# 07-ModuleControls.net
KiCad netlist of a schematic drawn in Altium Designer
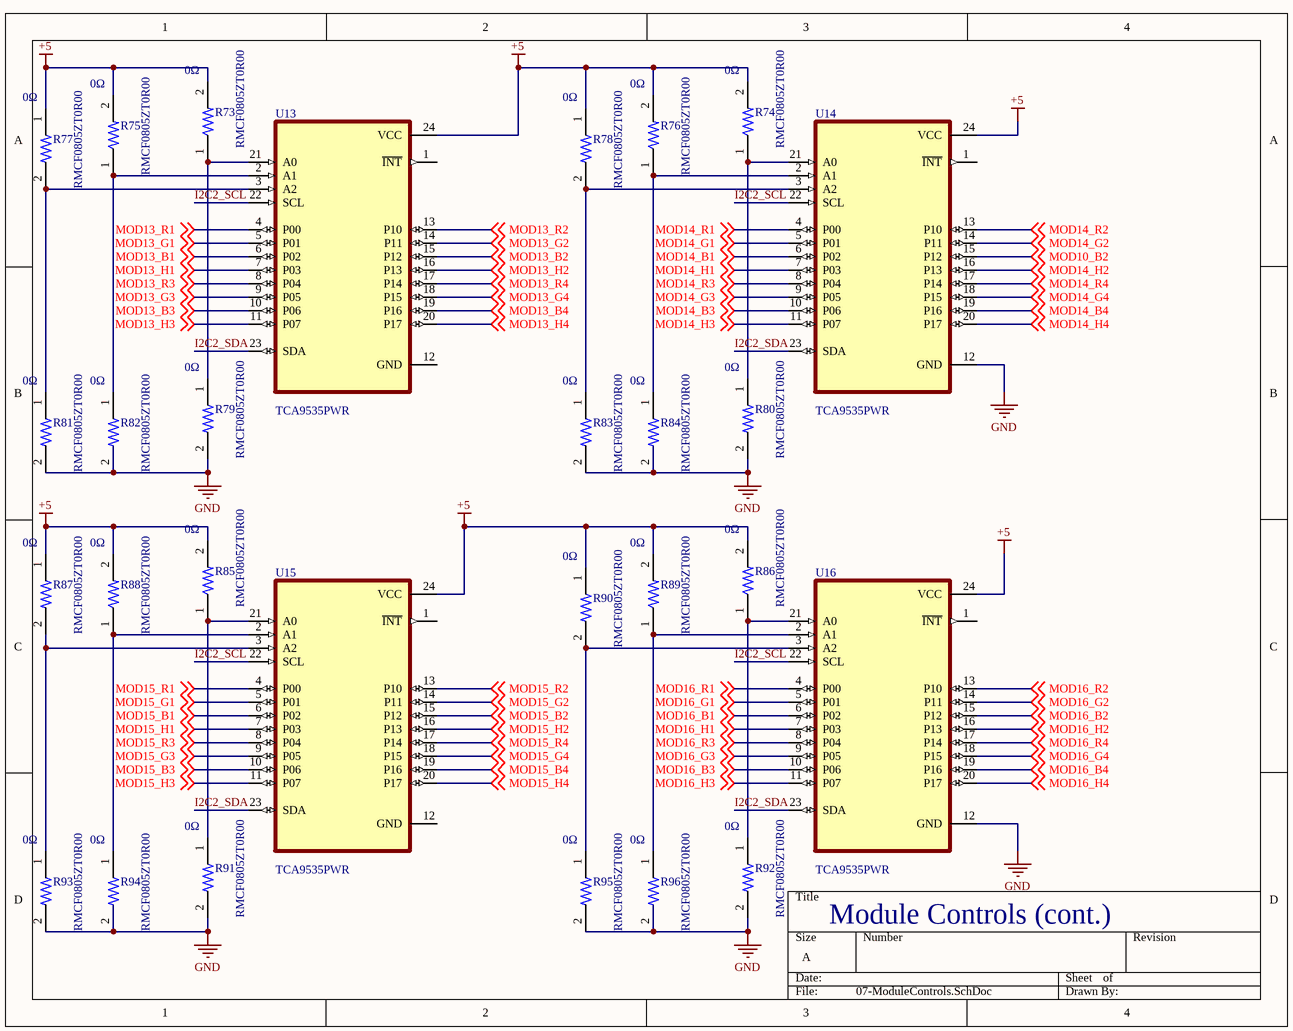
[diagram p0: 07-ModuleControls.SchDoc]

(export (version "E")
  (design (tool "Eeschema 10.0.6"))
  (components
    (comp (ref "R73")
      (value "RMCF0805ZT0R00")
      (footprint "RESC2012X60N")
      (description "0 Ohms Jumper 0.125W, 1/8W Chip Resistor 0805 (2012 Metric) Automotive AEC-Q200 Thick Film")
      (fields (field (name "MF") "Stackpole Electronics") (field (name "RESITANCE") "0Ω"))
      (libsource (lib "base-board") (part "RMCF0805ZT0R00"))
    )
    (comp (ref "R74")
      (value "RMCF0805ZT0R00")
      (footprint "RESC2012X60N")
      (description "0 Ohms Jumper 0.125W, 1/8W Chip Resistor 0805 (2012 Metric) Automotive AEC-Q200 Thick Film")
      (fields (field (name "MF") "Stackpole Electronics") (field (name "RESITANCE") "0Ω"))
      (libsource (lib "base-board") (part "RMCF0805ZT0R00"))
    )
    (comp (ref "R75")
      (value "RMCF0805ZT0R00")
      (footprint "RESC2012X60N")
      (description "0 Ohms Jumper 0.125W, 1/8W Chip Resistor 0805 (2012 Metric) Automotive AEC-Q200 Thick Film")
      (fields (field (name "MF") "Stackpole Electronics") (field (name "RESITANCE") "0Ω"))
      (libsource (lib "base-board") (part "RMCF0805ZT0R00"))
    )
    (comp (ref "R76")
      (value "RMCF0805ZT0R00")
      (footprint "RESC2012X60N")
      (description "0 Ohms Jumper 0.125W, 1/8W Chip Resistor 0805 (2012 Metric) Automotive AEC-Q200 Thick Film")
      (fields (field (name "MF") "Stackpole Electronics") (field (name "RESITANCE") "0Ω"))
      (libsource (lib "base-board") (part "RMCF0805ZT0R00"))
    )
    (comp (ref "R77")
      (value "RMCF0805ZT0R00")
      (footprint "RESC2012X60N")
      (description "0 Ohms Jumper 0.125W, 1/8W Chip Resistor 0805 (2012 Metric) Automotive AEC-Q200 Thick Film")
      (fields (field (name "MF") "Stackpole Electronics") (field (name "RESITANCE") "0Ω"))
      (libsource (lib "base-board") (part "RMCF0805ZT0R00"))
    )
    (comp (ref "R78")
      (value "RMCF0805ZT0R00")
      (footprint "RESC2012X60N")
      (description "0 Ohms Jumper 0.125W, 1/8W Chip Resistor 0805 (2012 Metric) Automotive AEC-Q200 Thick Film")
      (fields (field (name "MF") "Stackpole Electronics") (field (name "RESITANCE") "0Ω"))
      (libsource (lib "base-board") (part "RMCF0805ZT0R00"))
    )
    (comp (ref "R79")
      (value "RMCF0805ZT0R00")
      (footprint "RESC2012X60N")
      (description "0 Ohms Jumper 0.125W, 1/8W Chip Resistor 0805 (2012 Metric) Automotive AEC-Q200 Thick Film")
      (fields (field (name "MF") "Stackpole Electronics") (field (name "RESITANCE") "0Ω"))
      (libsource (lib "base-board") (part "RMCF0805ZT0R00"))
    )
    (comp (ref "R80")
      (value "RMCF0805ZT0R00")
      (footprint "RESC2012X60N")
      (description "0 Ohms Jumper 0.125W, 1/8W Chip Resistor 0805 (2012 Metric) Automotive AEC-Q200 Thick Film")
      (fields (field (name "MF") "Stackpole Electronics") (field (name "RESITANCE") "0Ω"))
      (libsource (lib "base-board") (part "RMCF0805ZT0R00"))
    )
    (comp (ref "R81")
      (value "RMCF0805ZT0R00")
      (footprint "RESC2012X60N")
      (description "0 Ohms Jumper 0.125W, 1/8W Chip Resistor 0805 (2012 Metric) Automotive AEC-Q200 Thick Film")
      (fields (field (name "MF") "Stackpole Electronics") (field (name "RESITANCE") "0Ω"))
      (libsource (lib "base-board") (part "RMCF0805ZT0R00"))
    )
    (comp (ref "R82")
      (value "RMCF0805ZT0R00")
      (footprint "RESC2012X60N")
      (description "0 Ohms Jumper 0.125W, 1/8W Chip Resistor 0805 (2012 Metric) Automotive AEC-Q200 Thick Film")
      (fields (field (name "MF") "Stackpole Electronics") (field (name "RESITANCE") "0Ω"))
      (libsource (lib "base-board") (part "RMCF0805ZT0R00"))
    )
    (comp (ref "R83")
      (value "RMCF0805ZT0R00")
      (footprint "RESC2012X60N")
      (description "0 Ohms Jumper 0.125W, 1/8W Chip Resistor 0805 (2012 Metric) Automotive AEC-Q200 Thick Film")
      (fields (field (name "MF") "Stackpole Electronics") (field (name "RESITANCE") "0Ω"))
      (libsource (lib "base-board") (part "RMCF0805ZT0R00"))
    )
    (comp (ref "R84")
      (value "RMCF0805ZT0R00")
      (footprint "RESC2012X60N")
      (description "0 Ohms Jumper 0.125W, 1/8W Chip Resistor 0805 (2012 Metric) Automotive AEC-Q200 Thick Film")
      (fields (field (name "MF") "Stackpole Electronics") (field (name "RESITANCE") "0Ω"))
      (libsource (lib "base-board") (part "RMCF0805ZT0R00"))
    )
    (comp (ref "R85")
      (value "RMCF0805ZT0R00")
      (footprint "RESC2012X60N")
      (description "0 Ohms Jumper 0.125W, 1/8W Chip Resistor 0805 (2012 Metric) Automotive AEC-Q200 Thick Film")
      (fields (field (name "MF") "Stackpole Electronics") (field (name "RESITANCE") "0Ω"))
      (libsource (lib "base-board") (part "RMCF0805ZT0R00"))
    )
    (comp (ref "R86")
      (value "RMCF0805ZT0R00")
      (footprint "RESC2012X60N")
      (description "0 Ohms Jumper 0.125W, 1/8W Chip Resistor 0805 (2012 Metric) Automotive AEC-Q200 Thick Film")
      (fields (field (name "MF") "Stackpole Electronics") (field (name "RESITANCE") "0Ω"))
      (libsource (lib "base-board") (part "RMCF0805ZT0R00"))
    )
    (comp (ref "R87")
      (value "RMCF0805ZT0R00")
      (footprint "RESC2012X60N")
      (description "0 Ohms Jumper 0.125W, 1/8W Chip Resistor 0805 (2012 Metric) Automotive AEC-Q200 Thick Film")
      (fields (field (name "MF") "Stackpole Electronics") (field (name "RESITANCE") "0Ω"))
      (libsource (lib "base-board") (part "RMCF0805ZT0R00"))
    )
    (comp (ref "R88")
      (value "RMCF0805ZT0R00")
      (footprint "RESC2012X60N")
      (description "0 Ohms Jumper 0.125W, 1/8W Chip Resistor 0805 (2012 Metric) Automotive AEC-Q200 Thick Film")
      (fields (field (name "MF") "Stackpole Electronics") (field (name "RESITANCE") "0Ω"))
      (libsource (lib "base-board") (part "RMCF0805ZT0R00"))
    )
    (comp (ref "R89")
      (value "RMCF0805ZT0R00")
      (footprint "RESC2012X60N")
      (description "0 Ohms Jumper 0.125W, 1/8W Chip Resistor 0805 (2012 Metric) Automotive AEC-Q200 Thick Film")
      (fields (field (name "MF") "Stackpole Electronics") (field (name "RESITANCE") "0Ω"))
      (libsource (lib "base-board") (part "RMCF0805ZT0R00"))
    )
    (comp (ref "R90")
      (value "RMCF0805ZT0R00")
      (footprint "RESC2012X60N")
      (description "0 Ohms Jumper 0.125W, 1/8W Chip Resistor 0805 (2012 Metric) Automotive AEC-Q200 Thick Film")
      (fields (field (name "MF") "Stackpole Electronics") (field (name "RESITANCE") "0Ω"))
      (libsource (lib "base-board") (part "RMCF0805ZT0R00"))
    )
    (comp (ref "R91")
      (value "RMCF0805ZT0R00")
      (footprint "RESC2012X60N")
      (description "0 Ohms Jumper 0.125W, 1/8W Chip Resistor 0805 (2012 Metric) Automotive AEC-Q200 Thick Film")
      (fields (field (name "MF") "Stackpole Electronics") (field (name "RESITANCE") "0Ω"))
      (libsource (lib "base-board") (part "RMCF0805ZT0R00"))
    )
    (comp (ref "R92")
      (value "RMCF0805ZT0R00")
      (footprint "RESC2012X60N")
      (description "0 Ohms Jumper 0.125W, 1/8W Chip Resistor 0805 (2012 Metric) Automotive AEC-Q200 Thick Film")
      (fields (field (name "MF") "Stackpole Electronics") (field (name "RESITANCE") "0Ω"))
      (libsource (lib "base-board") (part "RMCF0805ZT0R00"))
    )
    (comp (ref "R93")
      (value "RMCF0805ZT0R00")
      (footprint "RESC2012X60N")
      (description "0 Ohms Jumper 0.125W, 1/8W Chip Resistor 0805 (2012 Metric) Automotive AEC-Q200 Thick Film")
      (fields (field (name "MF") "Stackpole Electronics") (field (name "RESITANCE") "0Ω"))
      (libsource (lib "base-board") (part "RMCF0805ZT0R00"))
    )
    (comp (ref "R94")
      (value "RMCF0805ZT0R00")
      (footprint "RESC2012X60N")
      (description "0 Ohms Jumper 0.125W, 1/8W Chip Resistor 0805 (2012 Metric) Automotive AEC-Q200 Thick Film")
      (fields (field (name "MF") "Stackpole Electronics") (field (name "RESITANCE") "0Ω"))
      (libsource (lib "base-board") (part "RMCF0805ZT0R00"))
    )
    (comp (ref "R95")
      (value "RMCF0805ZT0R00")
      (footprint "RESC2012X60N")
      (description "0 Ohms Jumper 0.125W, 1/8W Chip Resistor 0805 (2012 Metric) Automotive AEC-Q200 Thick Film")
      (fields (field (name "MF") "Stackpole Electronics") (field (name "RESITANCE") "0Ω"))
      (libsource (lib "base-board") (part "RMCF0805ZT0R00"))
    )
    (comp (ref "R96")
      (value "RMCF0805ZT0R00")
      (footprint "RESC2012X60N")
      (description "0 Ohms Jumper 0.125W, 1/8W Chip Resistor 0805 (2012 Metric) Automotive AEC-Q200 Thick Film")
      (fields (field (name "MF") "Stackpole Electronics") (field (name "RESITANCE") "0Ω"))
      (libsource (lib "base-board") (part "RMCF0805ZT0R00"))
    )
    (comp (ref "U13")
      (value "TCA9535PWR")
      (footprint "SOP65P640X120-24N")
      (fields (field (name "MF") "Texas Instruments"))
      (libsource (lib "base-board") (part "TCA9535PWR"))
    )
    (comp (ref "U14")
      (value "TCA9535PWR")
      (footprint "SOP65P640X120-24N")
      (fields (field (name "MF") "Texas Instruments"))
      (libsource (lib "base-board") (part "TCA9535PWR"))
    )
    (comp (ref "U15")
      (value "TCA9535PWR")
      (footprint "SOP65P640X120-24N")
      (fields (field (name "MF") "Texas Instruments"))
      (libsource (lib "base-board") (part "TCA9535PWR"))
    )
    (comp (ref "U16")
      (value "TCA9535PWR")
      (footprint "SOP65P640X120-24N")
      (fields (field (name "MF") "Texas Instruments"))
      (libsource (lib "base-board") (part "TCA9535PWR"))
    )
  )
  (nets
    (net (code "1") (name "+5") (class "Default")
      (node (ref "R73") (pin "2") (pinfunction "2_2") (pintype "passive"))
      (node (ref "R74") (pin "2") (pinfunction "2_2") (pintype "passive"))
      (node (ref "R75") (pin "2") (pinfunction "2_2") (pintype "passive"))
      (node (ref "R76") (pin "2") (pinfunction "2_2") (pintype "passive"))
      (node (ref "R77") (pin "1") (pinfunction "1_1") (pintype "passive"))
      (node (ref "R78") (pin "1") (pinfunction "1_1") (pintype "passive"))
      (node (ref "R85") (pin "2") (pinfunction "2_2") (pintype "passive"))
      (node (ref "R86") (pin "2") (pinfunction "2_2") (pintype "passive"))
      (node (ref "R87") (pin "1") (pinfunction "1_1") (pintype "passive"))
      (node (ref "R88") (pin "2") (pinfunction "2_2") (pintype "passive"))
      (node (ref "R89") (pin "2") (pinfunction "2_2") (pintype "passive"))
      (node (ref "R90") (pin "1") (pinfunction "1_1") (pintype "passive"))
      (node (ref "U13") (pin "24") (pinfunction "VCC_24") (pintype "power_in"))
      (node (ref "U14") (pin "24") (pinfunction "VCC_24") (pintype "power_in"))
      (node (ref "U15") (pin "24") (pinfunction "VCC_24") (pintype "power_in"))
      (node (ref "U16") (pin "24") (pinfunction "VCC_24") (pintype "power_in"))
    )
    (net (code "2") (name "/I2C2_SCL") (class "Default")
      (node (ref "U13") (pin "22") (pinfunction "SCL_22") (pintype "input"))
      (node (ref "U14") (pin "22") (pinfunction "SCL_22") (pintype "input"))
      (node (ref "U15") (pin "22") (pinfunction "SCL_22") (pintype "input"))
      (node (ref "U16") (pin "22") (pinfunction "SCL_22") (pintype "input"))
    )
    (net (code "3") (name "/I2C2_SDA") (class "Default")
      (node (ref "U13") (pin "23") (pinfunction "SDA_23") (pintype "bidirectional"))
      (node (ref "U14") (pin "23") (pinfunction "SDA_23") (pintype "bidirectional"))
      (node (ref "U15") (pin "23") (pinfunction "SDA_23") (pintype "bidirectional"))
      (node (ref "U16") (pin "23") (pinfunction "SDA_23") (pintype "bidirectional"))
    )
    (net (code "4") (name "GND") (class "Default")
      (node (ref "R79") (pin "2") (pinfunction "2_2") (pintype "passive"))
      (node (ref "R80") (pin "2") (pinfunction "2_2") (pintype "passive"))
      (node (ref "R81") (pin "2") (pinfunction "2_2") (pintype "passive"))
      (node (ref "R82") (pin "2") (pinfunction "2_2") (pintype "passive"))
      (node (ref "R83") (pin "2") (pinfunction "2_2") (pintype "passive"))
      (node (ref "R84") (pin "2") (pinfunction "2_2") (pintype "passive"))
      (node (ref "R91") (pin "2") (pinfunction "2_2") (pintype "passive"))
      (node (ref "R92") (pin "2") (pinfunction "2_2") (pintype "passive"))
      (node (ref "R93") (pin "2") (pinfunction "2_2") (pintype "passive"))
      (node (ref "R94") (pin "2") (pinfunction "2_2") (pintype "passive"))
      (node (ref "R95") (pin "2") (pinfunction "2_2") (pintype "passive"))
      (node (ref "R96") (pin "2") (pinfunction "2_2") (pintype "passive"))
      (node (ref "U14") (pin "12") (pinfunction "GND_12") (pintype "power_in"))
      (node (ref "U16") (pin "12") (pinfunction "GND_12") (pintype "power_in"))
    )
    (net (code "5") (name "MOD10_B2") (class "Default")
      (node (ref "U14") (pin "15") (pinfunction "P12_15") (pintype "bidirectional"))
    )
    (net (code "6") (name "MOD13_B1") (class "Default")
      (node (ref "U13") (pin "6") (pinfunction "P02_6") (pintype "bidirectional"))
    )
    (net (code "7") (name "MOD13_B2") (class "Default")
      (node (ref "U13") (pin "15") (pinfunction "P12_15") (pintype "bidirectional"))
    )
    (net (code "8") (name "MOD13_B3") (class "Default")
      (node (ref "U13") (pin "10") (pinfunction "P06_10") (pintype "bidirectional"))
    )
    (net (code "9") (name "MOD13_B4") (class "Default")
      (node (ref "U13") (pin "19") (pinfunction "P16_19") (pintype "bidirectional"))
    )
    (net (code "10") (name "MOD13_G1") (class "Default")
      (node (ref "U13") (pin "5") (pinfunction "P01_5") (pintype "bidirectional"))
    )
    (net (code "11") (name "MOD13_G2") (class "Default")
      (node (ref "U13") (pin "14") (pinfunction "P11_14") (pintype "bidirectional"))
    )
    (net (code "12") (name "MOD13_G3") (class "Default")
      (node (ref "U13") (pin "9") (pinfunction "P05_9") (pintype "bidirectional"))
    )
    (net (code "13") (name "MOD13_G4") (class "Default")
      (node (ref "U13") (pin "18") (pinfunction "P15_18") (pintype "bidirectional"))
    )
    (net (code "14") (name "MOD13_H1") (class "Default")
      (node (ref "U13") (pin "7") (pinfunction "P03_7") (pintype "bidirectional"))
    )
    (net (code "15") (name "MOD13_H2") (class "Default")
      (node (ref "U13") (pin "16") (pinfunction "P13_16") (pintype "bidirectional"))
    )
    (net (code "16") (name "MOD13_H3") (class "Default")
      (node (ref "U13") (pin "11") (pinfunction "P07_11") (pintype "bidirectional"))
    )
    (net (code "17") (name "MOD13_H4") (class "Default")
      (node (ref "U13") (pin "20") (pinfunction "P17_20") (pintype "bidirectional"))
    )
    (net (code "18") (name "MOD13_R1") (class "Default")
      (node (ref "U13") (pin "4") (pinfunction "P00_4") (pintype "bidirectional"))
    )
    (net (code "19") (name "MOD13_R2") (class "Default")
      (node (ref "U13") (pin "13") (pinfunction "P10_13") (pintype "bidirectional"))
    )
    (net (code "20") (name "MOD13_R3") (class "Default")
      (node (ref "U13") (pin "8") (pinfunction "P04_8") (pintype "bidirectional"))
    )
    (net (code "21") (name "MOD13_R4") (class "Default")
      (node (ref "U13") (pin "17") (pinfunction "P14_17") (pintype "bidirectional"))
    )
    (net (code "22") (name "MOD14_B1") (class "Default")
      (node (ref "U14") (pin "6") (pinfunction "P02_6") (pintype "bidirectional"))
    )
    (net (code "23") (name "MOD14_B3") (class "Default")
      (node (ref "U14") (pin "10") (pinfunction "P06_10") (pintype "bidirectional"))
    )
    (net (code "24") (name "MOD14_B4") (class "Default")
      (node (ref "U14") (pin "19") (pinfunction "P16_19") (pintype "bidirectional"))
    )
    (net (code "25") (name "MOD14_G1") (class "Default")
      (node (ref "U14") (pin "5") (pinfunction "P01_5") (pintype "bidirectional"))
    )
    (net (code "26") (name "MOD14_G2") (class "Default")
      (node (ref "U14") (pin "14") (pinfunction "P11_14") (pintype "bidirectional"))
    )
    (net (code "27") (name "MOD14_G3") (class "Default")
      (node (ref "U14") (pin "9") (pinfunction "P05_9") (pintype "bidirectional"))
    )
    (net (code "28") (name "MOD14_G4") (class "Default")
      (node (ref "U14") (pin "18") (pinfunction "P15_18") (pintype "bidirectional"))
    )
    (net (code "29") (name "MOD14_H1") (class "Default")
      (node (ref "U14") (pin "7") (pinfunction "P03_7") (pintype "bidirectional"))
    )
    (net (code "30") (name "MOD14_H2") (class "Default")
      (node (ref "U14") (pin "16") (pinfunction "P13_16") (pintype "bidirectional"))
    )
    (net (code "31") (name "MOD14_H3") (class "Default")
      (node (ref "U14") (pin "11") (pinfunction "P07_11") (pintype "bidirectional"))
    )
    (net (code "32") (name "MOD14_H4") (class "Default")
      (node (ref "U14") (pin "20") (pinfunction "P17_20") (pintype "bidirectional"))
    )
    (net (code "33") (name "MOD14_R1") (class "Default")
      (node (ref "U14") (pin "4") (pinfunction "P00_4") (pintype "bidirectional"))
    )
    (net (code "34") (name "MOD14_R2") (class "Default")
      (node (ref "U14") (pin "13") (pinfunction "P10_13") (pintype "bidirectional"))
    )
    (net (code "35") (name "MOD14_R3") (class "Default")
      (node (ref "U14") (pin "8") (pinfunction "P04_8") (pintype "bidirectional"))
    )
    (net (code "36") (name "MOD14_R4") (class "Default")
      (node (ref "U14") (pin "17") (pinfunction "P14_17") (pintype "bidirectional"))
    )
    (net (code "37") (name "MOD15_B1") (class "Default")
      (node (ref "U15") (pin "6") (pinfunction "P02_6") (pintype "bidirectional"))
    )
    (net (code "38") (name "MOD15_B2") (class "Default")
      (node (ref "U15") (pin "15") (pinfunction "P12_15") (pintype "bidirectional"))
    )
    (net (code "39") (name "MOD15_B3") (class "Default")
      (node (ref "U15") (pin "10") (pinfunction "P06_10") (pintype "bidirectional"))
    )
    (net (code "40") (name "MOD15_B4") (class "Default")
      (node (ref "U15") (pin "19") (pinfunction "P16_19") (pintype "bidirectional"))
    )
    (net (code "41") (name "MOD15_G1") (class "Default")
      (node (ref "U15") (pin "5") (pinfunction "P01_5") (pintype "bidirectional"))
    )
    (net (code "42") (name "MOD15_G2") (class "Default")
      (node (ref "U15") (pin "14") (pinfunction "P11_14") (pintype "bidirectional"))
    )
    (net (code "43") (name "MOD15_G3") (class "Default")
      (node (ref "U15") (pin "9") (pinfunction "P05_9") (pintype "bidirectional"))
    )
    (net (code "44") (name "MOD15_G4") (class "Default")
      (node (ref "U15") (pin "18") (pinfunction "P15_18") (pintype "bidirectional"))
    )
    (net (code "45") (name "MOD15_H1") (class "Default")
      (node (ref "U15") (pin "7") (pinfunction "P03_7") (pintype "bidirectional"))
    )
    (net (code "46") (name "MOD15_H2") (class "Default")
      (node (ref "U15") (pin "16") (pinfunction "P13_16") (pintype "bidirectional"))
    )
    (net (code "47") (name "MOD15_H3") (class "Default")
      (node (ref "U15") (pin "11") (pinfunction "P07_11") (pintype "bidirectional"))
    )
    (net (code "48") (name "MOD15_H4") (class "Default")
      (node (ref "U15") (pin "20") (pinfunction "P17_20") (pintype "bidirectional"))
    )
    (net (code "49") (name "MOD15_R1") (class "Default")
      (node (ref "U15") (pin "4") (pinfunction "P00_4") (pintype "bidirectional"))
    )
    (net (code "50") (name "MOD15_R2") (class "Default")
      (node (ref "U15") (pin "13") (pinfunction "P10_13") (pintype "bidirectional"))
    )
    (net (code "51") (name "MOD15_R3") (class "Default")
      (node (ref "U15") (pin "8") (pinfunction "P04_8") (pintype "bidirectional"))
    )
    (net (code "52") (name "MOD15_R4") (class "Default")
      (node (ref "U15") (pin "17") (pinfunction "P14_17") (pintype "bidirectional"))
    )
    (net (code "53") (name "MOD16_B1") (class "Default")
      (node (ref "U16") (pin "6") (pinfunction "P02_6") (pintype "bidirectional"))
    )
    (net (code "54") (name "MOD16_B2") (class "Default")
      (node (ref "U16") (pin "15") (pinfunction "P12_15") (pintype "bidirectional"))
    )
    (net (code "55") (name "MOD16_B3") (class "Default")
      (node (ref "U16") (pin "10") (pinfunction "P06_10") (pintype "bidirectional"))
    )
    (net (code "56") (name "MOD16_B4") (class "Default")
      (node (ref "U16") (pin "19") (pinfunction "P16_19") (pintype "bidirectional"))
    )
    (net (code "57") (name "MOD16_G1") (class "Default")
      (node (ref "U16") (pin "5") (pinfunction "P01_5") (pintype "bidirectional"))
    )
    (net (code "58") (name "MOD16_G2") (class "Default")
      (node (ref "U16") (pin "14") (pinfunction "P11_14") (pintype "bidirectional"))
    )
    (net (code "59") (name "MOD16_G3") (class "Default")
      (node (ref "U16") (pin "9") (pinfunction "P05_9") (pintype "bidirectional"))
    )
    (net (code "60") (name "MOD16_G4") (class "Default")
      (node (ref "U16") (pin "18") (pinfunction "P15_18") (pintype "bidirectional"))
    )
    (net (code "61") (name "MOD16_H1") (class "Default")
      (node (ref "U16") (pin "7") (pinfunction "P03_7") (pintype "bidirectional"))
    )
    (net (code "62") (name "MOD16_H2") (class "Default")
      (node (ref "U16") (pin "16") (pinfunction "P13_16") (pintype "bidirectional"))
    )
    (net (code "63") (name "MOD16_H3") (class "Default")
      (node (ref "U16") (pin "11") (pinfunction "P07_11") (pintype "bidirectional"))
    )
    (net (code "64") (name "MOD16_H4") (class "Default")
      (node (ref "U16") (pin "20") (pinfunction "P17_20") (pintype "bidirectional"))
    )
    (net (code "65") (name "MOD16_R1") (class "Default")
      (node (ref "U16") (pin "4") (pinfunction "P00_4") (pintype "bidirectional"))
    )
    (net (code "66") (name "MOD16_R2") (class "Default")
      (node (ref "U16") (pin "13") (pinfunction "P10_13") (pintype "bidirectional"))
    )
    (net (code "67") (name "MOD16_R3") (class "Default")
      (node (ref "U16") (pin "8") (pinfunction "P04_8") (pintype "bidirectional"))
    )
    (net (code "68") (name "MOD16_R4") (class "Default")
      (node (ref "U16") (pin "17") (pinfunction "P14_17") (pintype "bidirectional"))
    )
    (net (code "69") (name "Net-(U13-A0)") (class "Default")
      (node (ref "R73") (pin "1") (pinfunction "1_1") (pintype "passive"))
      (node (ref "R79") (pin "1") (pinfunction "1_1") (pintype "passive"))
      (node (ref "U13") (pin "21") (pinfunction "A0_21") (pintype "input"))
    )
    (net (code "70") (name "Net-(U13-A1)") (class "Default")
      (node (ref "R75") (pin "1") (pinfunction "1_1") (pintype "passive"))
      (node (ref "R82") (pin "1") (pinfunction "1_1") (pintype "passive"))
      (node (ref "U13") (pin "2") (pinfunction "A1_2") (pintype "input"))
    )
    (net (code "71") (name "Net-(U13-A2)") (class "Default")
      (node (ref "R77") (pin "2") (pinfunction "2_2") (pintype "passive"))
      (node (ref "R81") (pin "1") (pinfunction "1_1") (pintype "passive"))
      (node (ref "U13") (pin "3") (pinfunction "A2_3") (pintype "input"))
    )
    (net (code "72") (name "Net-(U14-A0)") (class "Default")
      (node (ref "R74") (pin "1") (pinfunction "1_1") (pintype "passive"))
      (node (ref "R80") (pin "1") (pinfunction "1_1") (pintype "passive"))
      (node (ref "U14") (pin "21") (pinfunction "A0_21") (pintype "input"))
    )
    (net (code "73") (name "Net-(U14-A1)") (class "Default")
      (node (ref "R76") (pin "1") (pinfunction "1_1") (pintype "passive"))
      (node (ref "R84") (pin "1") (pinfunction "1_1") (pintype "passive"))
      (node (ref "U14") (pin "2") (pinfunction "A1_2") (pintype "input"))
    )
    (net (code "74") (name "Net-(U14-A2)") (class "Default")
      (node (ref "R78") (pin "2") (pinfunction "2_2") (pintype "passive"))
      (node (ref "R83") (pin "1") (pinfunction "1_1") (pintype "passive"))
      (node (ref "U14") (pin "3") (pinfunction "A2_3") (pintype "input"))
    )
    (net (code "75") (name "Net-(U15-A0)") (class "Default")
      (node (ref "R85") (pin "1") (pinfunction "1_1") (pintype "passive"))
      (node (ref "R91") (pin "1") (pinfunction "1_1") (pintype "passive"))
      (node (ref "U15") (pin "21") (pinfunction "A0_21") (pintype "input"))
    )
    (net (code "76") (name "Net-(U15-A1)") (class "Default")
      (node (ref "R88") (pin "1") (pinfunction "1_1") (pintype "passive"))
      (node (ref "R94") (pin "1") (pinfunction "1_1") (pintype "passive"))
      (node (ref "U15") (pin "2") (pinfunction "A1_2") (pintype "input"))
    )
    (net (code "77") (name "Net-(U15-A2)") (class "Default")
      (node (ref "R87") (pin "2") (pinfunction "2_2") (pintype "passive"))
      (node (ref "R93") (pin "1") (pinfunction "1_1") (pintype "passive"))
      (node (ref "U15") (pin "3") (pinfunction "A2_3") (pintype "input"))
    )
    (net (code "78") (name "Net-(U16-A0)") (class "Default")
      (node (ref "R86") (pin "1") (pinfunction "1_1") (pintype "passive"))
      (node (ref "R92") (pin "1") (pinfunction "1_1") (pintype "passive"))
      (node (ref "U16") (pin "21") (pinfunction "A0_21") (pintype "input"))
    )
    (net (code "79") (name "Net-(U16-A1)") (class "Default")
      (node (ref "R89") (pin "1") (pinfunction "1_1") (pintype "passive"))
      (node (ref "R96") (pin "1") (pinfunction "1_1") (pintype "passive"))
      (node (ref "U16") (pin "2") (pinfunction "A1_2") (pintype "input"))
    )
    (net (code "80") (name "Net-(U16-A2)") (class "Default")
      (node (ref "R90") (pin "2") (pinfunction "2_2") (pintype "passive"))
      (node (ref "R95") (pin "1") (pinfunction "1_1") (pintype "passive"))
      (node (ref "U16") (pin "3") (pinfunction "A2_3") (pintype "input"))
    )
    (net (code "81") (name "unconnected-(U13-GND-Pad12)") (class "Default")
      (node (ref "U13") (pin "12") (pinfunction "GND_12") (pintype "power_in"))
    )
    (net (code "82") (name "unconnected-(U13-~{INT}-Pad1)") (class "Default")
      (node (ref "U13") (pin "1") (pinfunction "~{INT}_1") (pintype "output"))
    )
    (net (code "83") (name "unconnected-(U14-~{INT}-Pad1)") (class "Default")
      (node (ref "U14") (pin "1") (pinfunction "~{INT}_1") (pintype "output"))
    )
    (net (code "84") (name "unconnected-(U15-GND-Pad12)") (class "Default")
      (node (ref "U15") (pin "12") (pinfunction "GND_12") (pintype "power_in"))
    )
    (net (code "85") (name "unconnected-(U15-~{INT}-Pad1)") (class "Default")
      (node (ref "U15") (pin "1") (pinfunction "~{INT}_1") (pintype "output"))
    )
    (net (code "86") (name "unconnected-(U16-~{INT}-Pad1)") (class "Default")
      (node (ref "U16") (pin "1") (pinfunction "~{INT}_1") (pintype "output"))
    )
  )
)
